# ESP-01S.net
KiCad netlist of a schematic drawn in Altium Designer
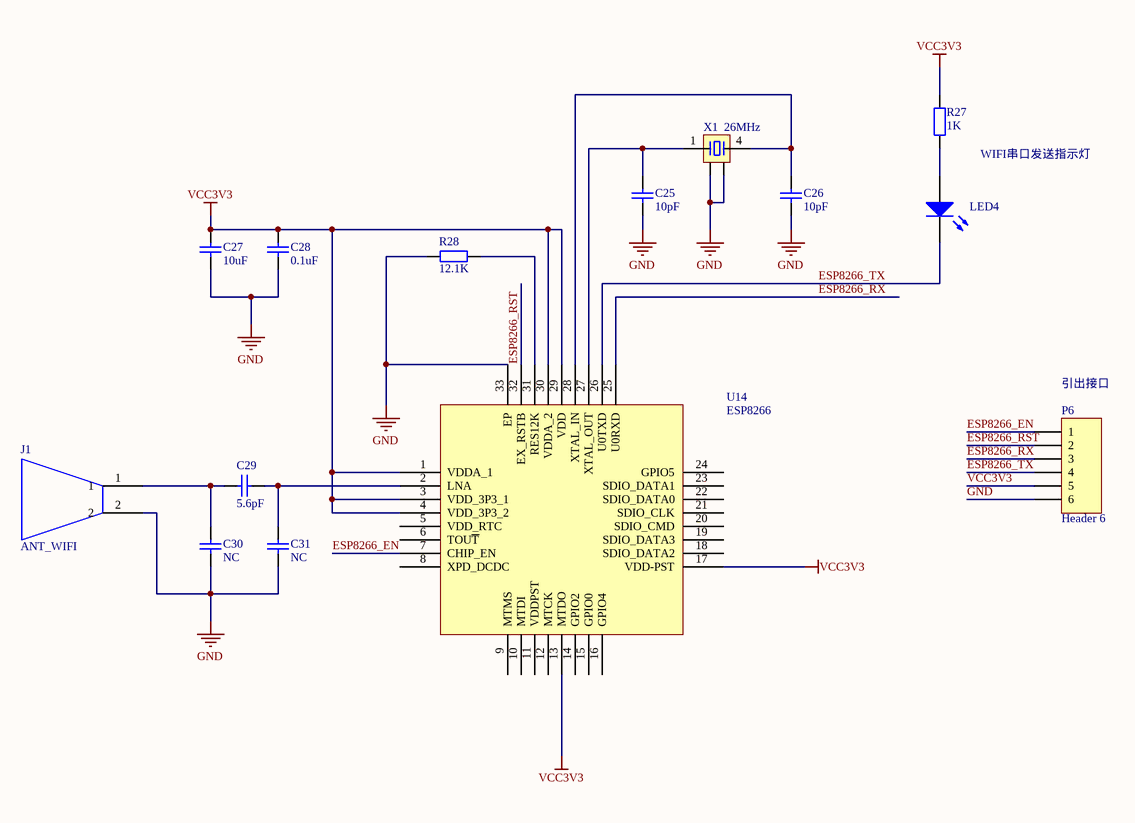
[diagram p0: ESP-01S.SchDoc]

(export (version "E")
  (design (tool "Eeschema 10.0.6"))
  (components
    (comp (ref "C25")
      (value "10pF")
      (footprint "C0805_L")
      (description "贴片电容/MLCC电容")
      (libsource (lib "0.1 - 电阻-电容-电感-保险丝-晶振-晶体-磁珠-电位器-法拉电容-馈通电容") (part "C"))
    )
    (comp (ref "C26")
      (value "10pF")
      (footprint "C0805_L")
      (description "贴片电容/MLCC电容")
      (libsource (lib "0.1 - 电阻-电容-电感-保险丝-晶振-晶体-磁珠-电位器-法拉电容-馈通电容") (part "C"))
    )
    (comp (ref "C27")
      (value "10uF")
      (footprint "C0805_L")
      (description "贴片电容/MLCC电容")
      (libsource (lib "0.1 - 电阻-电容-电感-保险丝-晶振-晶体-磁珠-电位器-法拉电容-馈通电容") (part "C"))
    )
    (comp (ref "C28")
      (value "0.1uF")
      (footprint "C0805_L")
      (description "贴片电容/MLCC电容")
      (libsource (lib "0.1 - 电阻-电容-电感-保险丝-晶振-晶体-磁珠-电位器-法拉电容-馈通电容") (part "C"))
    )
    (comp (ref "C29")
      (value "5.6pF")
      (footprint "C0805_L")
      (description "贴片电容/MLCC电容")
      (libsource (lib "0.1 - 电阻-电容-电感-保险丝-晶振-晶体-磁珠-电位器-法拉电容-馈通电容") (part "C"))
    )
    (comp (ref "C30")
      (value "NC")
      (footprint "C0805_L")
      (description "贴片电容/MLCC电容")
      (libsource (lib "0.1 - 电阻-电容-电感-保险丝-晶振-晶体-磁珠-电位器-法拉电容-馈通电容") (part "C"))
    )
    (comp (ref "C31")
      (value "NC")
      (footprint "C0805_L")
      (description "贴片电容/MLCC电容")
      (libsource (lib "0.1 - 电阻-电容-电感-保险丝-晶振-晶体-磁珠-电位器-法拉电容-馈通电容") (part "C"))
    )
    (comp (ref "J1") (value "ANT_WIFI") (libsource (lib "ESP-01S") (part "ANT_WIFI")))
    (comp (ref "LED4")
      (value "红色")
      (footprint "LED0805_G")
      (description "贴片LED")
      (libsource (lib "0.3 - LED发光二极管-IR二极管_接收管-光耦") (part "LED"))
    )
    (comp (ref "P6")
      (value "Header 6")
      (footprint "HDR1X6")
      (description "Header, 6-Pin")
      (fields (field (name "PUBLISHER") "Altium Limited"))
      (libsource (lib "Miscellaneous Connectors") (part "Header 6"))
    )
    (comp (ref "R27")
      (value "1K")
      (footprint "R0805_L")
      (description "贴片电阻")
      (libsource (lib "0.1 - 电阻-电容-电感-保险丝-晶振-晶体-磁珠-电位器-法拉电容-馈通电容") (part "R"))
    )
    (comp (ref "R28")
      (value "12.1K")
      (footprint "R0805_L")
      (description "贴片电阻")
      (libsource (lib "0.1 - 电阻-电容-电感-保险丝-晶振-晶体-磁珠-电位器-法拉电容-馈通电容") (part "R"))
    )
    (comp (ref "U14") (value "ESP8266") (libsource (lib "ESP-01S") (part "ESP8266")))
    (comp (ref "X1")
      (value "26MHz")
      (footprint "MC-146")
      (description "MC系列4脚无源晶振(谐振器）")
      (libsource (lib "0.1 - 电阻-电容-电感-保险丝-晶振-晶体-磁珠-电位器-法拉电容-馈通电容") (part "XTAL-MC-4P"))
    )
  )
  (nets
    (net (code "1") (name "/ESP8266_EN") (class "Default")
      (node (ref "P6") (pin "1") (pinfunction "1_1") (pintype "passive"))
      (node (ref "U14") (pin "7") (pinfunction "CHIP_EN_7") (pintype "passive"))
    )
    (net (code "2") (name "/ESP8266_RST") (class "Default")
      (node (ref "P6") (pin "2") (pinfunction "2_2") (pintype "passive"))
      (node (ref "U14") (pin "32") (pinfunction "EX_RSTB_32") (pintype "passive"))
    )
    (net (code "3") (name "/ESP8266_RX") (class "Default")
      (node (ref "P6") (pin "3") (pinfunction "3_3") (pintype "passive"))
      (node (ref "U14") (pin "25") (pinfunction "U0RXD_25") (pintype "passive"))
    )
    (net (code "4") (name "/ESP8266_TX") (class "Default")
      (node (ref "LED4") (pin "2") (pinfunction "K_2") (pintype "passive"))
      (node (ref "P6") (pin "4") (pinfunction "4_4") (pintype "passive"))
      (node (ref "U14") (pin "26") (pinfunction "U0TXD_26") (pintype "passive"))
    )
    (net (code "5") (name "GND") (class "Default")
      (node (ref "C25") (pin "1") (pinfunction "1_1") (pintype "passive"))
      (node (ref "C26") (pin "1") (pinfunction "1_1") (pintype "passive"))
      (node (ref "C27") (pin "1") (pinfunction "1_1") (pintype "passive"))
      (node (ref "C28") (pin "1") (pinfunction "1_1") (pintype "passive"))
      (node (ref "C30") (pin "1") (pinfunction "1_1") (pintype "passive"))
      (node (ref "C31") (pin "1") (pinfunction "1_1") (pintype "passive"))
      (node (ref "J1") (pin "2") (pinfunction "2_2") (pintype "passive"))
      (node (ref "P6") (pin "6") (pinfunction "6_6") (pintype "passive"))
      (node (ref "R28") (pin "1") (pinfunction "1_1") (pintype "passive"))
      (node (ref "U14") (pin "33") (pinfunction "EP_33") (pintype "passive"))
      (node (ref "X1") (pin "2") (pinfunction "2_2") (pintype "passive"))
      (node (ref "X1") (pin "3") (pinfunction "3_3") (pintype "passive"))
    )
    (net (code "6") (name "Net-(C29-Pad2)") (class "Default")
      (node (ref "C29") (pin "2") (pinfunction "2_2") (pintype "passive"))
      (node (ref "C30") (pin "2") (pinfunction "2_2") (pintype "passive"))
      (node (ref "J1") (pin "1") (pinfunction "1_1") (pintype "passive"))
    )
    (net (code "7") (name "Net-(LED4-A)") (class "Default")
      (node (ref "LED4") (pin "1") (pinfunction "A_1") (pintype "passive"))
      (node (ref "R27") (pin "1") (pinfunction "1_1") (pintype "passive"))
    )
    (net (code "8") (name "Net-(U14-LNA)") (class "Default")
      (node (ref "C29") (pin "1") (pinfunction "1_1") (pintype "passive"))
      (node (ref "C31") (pin "2") (pinfunction "2_2") (pintype "passive"))
      (node (ref "U14") (pin "2") (pinfunction "LNA_2") (pintype "passive"))
    )
    (net (code "9") (name "Net-(U14-RES12K)") (class "Default")
      (node (ref "R28") (pin "2") (pinfunction "2_2") (pintype "passive"))
      (node (ref "U14") (pin "31") (pinfunction "RES12K_31") (pintype "passive"))
    )
    (net (code "10") (name "Net-(U14-XTAL_IN)") (class "Default")
      (node (ref "C26") (pin "2") (pinfunction "2_2") (pintype "passive"))
      (node (ref "U14") (pin "28") (pinfunction "XTAL_IN_28") (pintype "passive"))
      (node (ref "X1") (pin "4") (pinfunction "4_4") (pintype "passive"))
    )
    (net (code "11") (name "Net-(U14-XTAL_OUT)") (class "Default")
      (node (ref "C25") (pin "2") (pinfunction "2_2") (pintype "passive"))
      (node (ref "U14") (pin "27") (pinfunction "XTAL_OUT_27") (pintype "passive"))
      (node (ref "X1") (pin "1") (pinfunction "1_1") (pintype "passive"))
    )
    (net (code "12") (name "VCC3V3") (class "Default")
      (node (ref "C27") (pin "2") (pinfunction "2_2") (pintype "passive"))
      (node (ref "C28") (pin "2") (pinfunction "2_2") (pintype "passive"))
      (node (ref "P6") (pin "5") (pinfunction "5_5") (pintype "passive"))
      (node (ref "R27") (pin "2") (pinfunction "2_2") (pintype "passive"))
      (node (ref "U14") (pin "1") (pinfunction "VDDA_1_1") (pintype "passive"))
      (node (ref "U14") (pin "13") (pinfunction "MTDO_13") (pintype "passive"))
      (node (ref "U14") (pin "17") (pinfunction "VDD-PST_17") (pintype "passive"))
      (node (ref "U14") (pin "29") (pinfunction "VDD_29") (pintype "passive"))
      (node (ref "U14") (pin "3") (pinfunction "VDD_3P3_1_3") (pintype "passive"))
      (node (ref "U14") (pin "30") (pinfunction "VDDA_2_30") (pintype "passive"))
      (node (ref "U14") (pin "4") (pinfunction "VDD_3P3_2_4") (pintype "passive"))
    )
    (net (code "13") (name "unconnected-(U14-GPIO0-Pad15)") (class "Default")
      (node (ref "U14") (pin "15") (pinfunction "GPIO0_15") (pintype "passive"))
    )
    (net (code "14") (name "unconnected-(U14-GPIO2-Pad14)") (class "Default")
      (node (ref "U14") (pin "14") (pinfunction "GPIO2_14") (pintype "passive"))
    )
    (net (code "15") (name "unconnected-(U14-GPIO4-Pad16)") (class "Default")
      (node (ref "U14") (pin "16") (pinfunction "GPIO4_16") (pintype "passive"))
    )
    (net (code "16") (name "unconnected-(U14-GPIO5-Pad24)") (class "Default")
      (node (ref "U14") (pin "24") (pinfunction "GPIO5_24") (pintype "passive"))
    )
    (net (code "17") (name "unconnected-(U14-MTCK-Pad12)") (class "Default")
      (node (ref "U14") (pin "12") (pinfunction "MTCK_12") (pintype "passive"))
    )
    (net (code "18") (name "unconnected-(U14-MTDI-Pad10)") (class "Default")
      (node (ref "U14") (pin "10") (pinfunction "MTDI_10") (pintype "passive"))
    )
    (net (code "19") (name "unconnected-(U14-MTMS-Pad9)") (class "Default")
      (node (ref "U14") (pin "9") (pinfunction "MTMS_9") (pintype "passive"))
    )
    (net (code "20") (name "unconnected-(U14-SDIO_CLK-Pad21)") (class "Default")
      (node (ref "U14") (pin "21") (pinfunction "SDIO_CLK_21") (pintype "passive"))
    )
    (net (code "21") (name "unconnected-(U14-SDIO_CMD-Pad20)") (class "Default")
      (node (ref "U14") (pin "20") (pinfunction "SDIO_CMD_20") (pintype "passive"))
    )
    (net (code "22") (name "unconnected-(U14-SDIO_DATA0-Pad22)") (class "Default")
      (node (ref "U14") (pin "22") (pinfunction "SDIO_DATA0_22") (pintype "passive"))
    )
    (net (code "23") (name "unconnected-(U14-SDIO_DATA1-Pad23)") (class "Default")
      (node (ref "U14") (pin "23") (pinfunction "SDIO_DATA1_23") (pintype "passive"))
    )
    (net (code "24") (name "unconnected-(U14-SDIO_DATA2-Pad18)") (class "Default")
      (node (ref "U14") (pin "18") (pinfunction "SDIO_DATA2_18") (pintype "passive"))
    )
    (net (code "25") (name "unconnected-(U14-SDIO_DATA3-Pad19)") (class "Default")
      (node (ref "U14") (pin "19") (pinfunction "SDIO_DATA3_19") (pintype "passive"))
    )
    (net (code "26") (name "unconnected-(U14-TOU~{T}-Pad6)") (class "Default")
      (node (ref "U14") (pin "6") (pinfunction "TOU~{T}_6") (pintype "passive"))
    )
    (net (code "27") (name "unconnected-(U14-VDDPST-Pad11)") (class "Default")
      (node (ref "U14") (pin "11") (pinfunction "VDDPST_11") (pintype "passive"))
    )
    (net (code "28") (name "unconnected-(U14-VDD_RTC-Pad5)") (class "Default")
      (node (ref "U14") (pin "5") (pinfunction "VDD_RTC_5") (pintype "passive"))
    )
    (net (code "29") (name "unconnected-(U14-XPD_DCDC-Pad8)") (class "Default")
      (node (ref "U14") (pin "8") (pinfunction "XPD_DCDC_8") (pintype "passive"))
    )
  )
)
